# TSTBTN_Sheet.net
KiCad netlist of a schematic drawn in Altium Designer
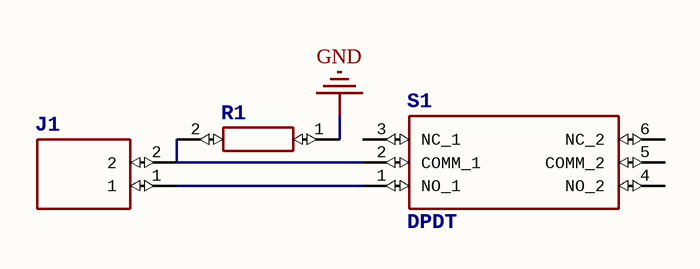
[diagram p0: TSTBTN_Sheet.SchDoc]

(export (version "E")
  (design (tool "Eeschema 10.0.6"))
  (components
    (comp (ref "J1")
      (value "~")
      (footprint "2518086")
      (fields (field (name "MANUFACTURER_PART_NUMBER") "251-8086"))
      (libsource (lib "251-8086") (part "251-8086"))
    )
    (comp (ref "R1")
      (value "~")
      (footprint "RESC2012X65N")
      (fields (field (name "MANUFACTURER_PART_NUMBER") "CRG0805F10K"))
      (libsource (lib "125-1189") (part "CRG0805F10K"))
    )
    (comp (ref "S1")
      (value "DPDT")
      (footprint "7346763")
      (fields (field (name "MANUFACTURER_PART_NUMBER") "734-6763"))
      (libsource (lib "734-6763") (part "734-6763"))
    )
  )
  (nets
    (net (code "1") (name "GND") (class "Default")
      (node (ref "R1") (pin "1") (pinfunction "1_1") (pintype "bidirectional"))
    )
    (net (code "2") (name "Net-(S1-COMM_1)") (class "Default")
      (node (ref "J1") (pin "2") (pinfunction "2_2") (pintype "bidirectional"))
      (node (ref "R1") (pin "2") (pinfunction "2_2") (pintype "bidirectional"))
      (node (ref "S1") (pin "2") (pinfunction "COMM_1_2") (pintype "bidirectional"))
    )
    (net (code "3") (name "Net-(S1-NO_1)") (class "Default")
      (node (ref "J1") (pin "1") (pinfunction "1_1") (pintype "bidirectional"))
      (node (ref "S1") (pin "1") (pinfunction "NO_1_1") (pintype "bidirectional"))
    )
    (net (code "4") (name "unconnected-(S1-COMM_2-Pad5)") (class "Default")
      (node (ref "S1") (pin "5") (pinfunction "COMM_2_5") (pintype "bidirectional"))
    )
    (net (code "5") (name "unconnected-(S1-NC_1-Pad3)") (class "Default")
      (node (ref "S1") (pin "3") (pinfunction "NC_1_3") (pintype "bidirectional"))
    )
    (net (code "6") (name "unconnected-(S1-NC_2-Pad6)") (class "Default")
      (node (ref "S1") (pin "6") (pinfunction "NC_2_6") (pintype "bidirectional"))
    )
    (net (code "7") (name "unconnected-(S1-NO_2-Pad4)") (class "Default")
      (node (ref "S1") (pin "4") (pinfunction "NO_2_4") (pintype "bidirectional"))
    )
  )
)
